# AMS_TNN_V1_0.net
KiCad netlist of a schematic drawn in EAGLE
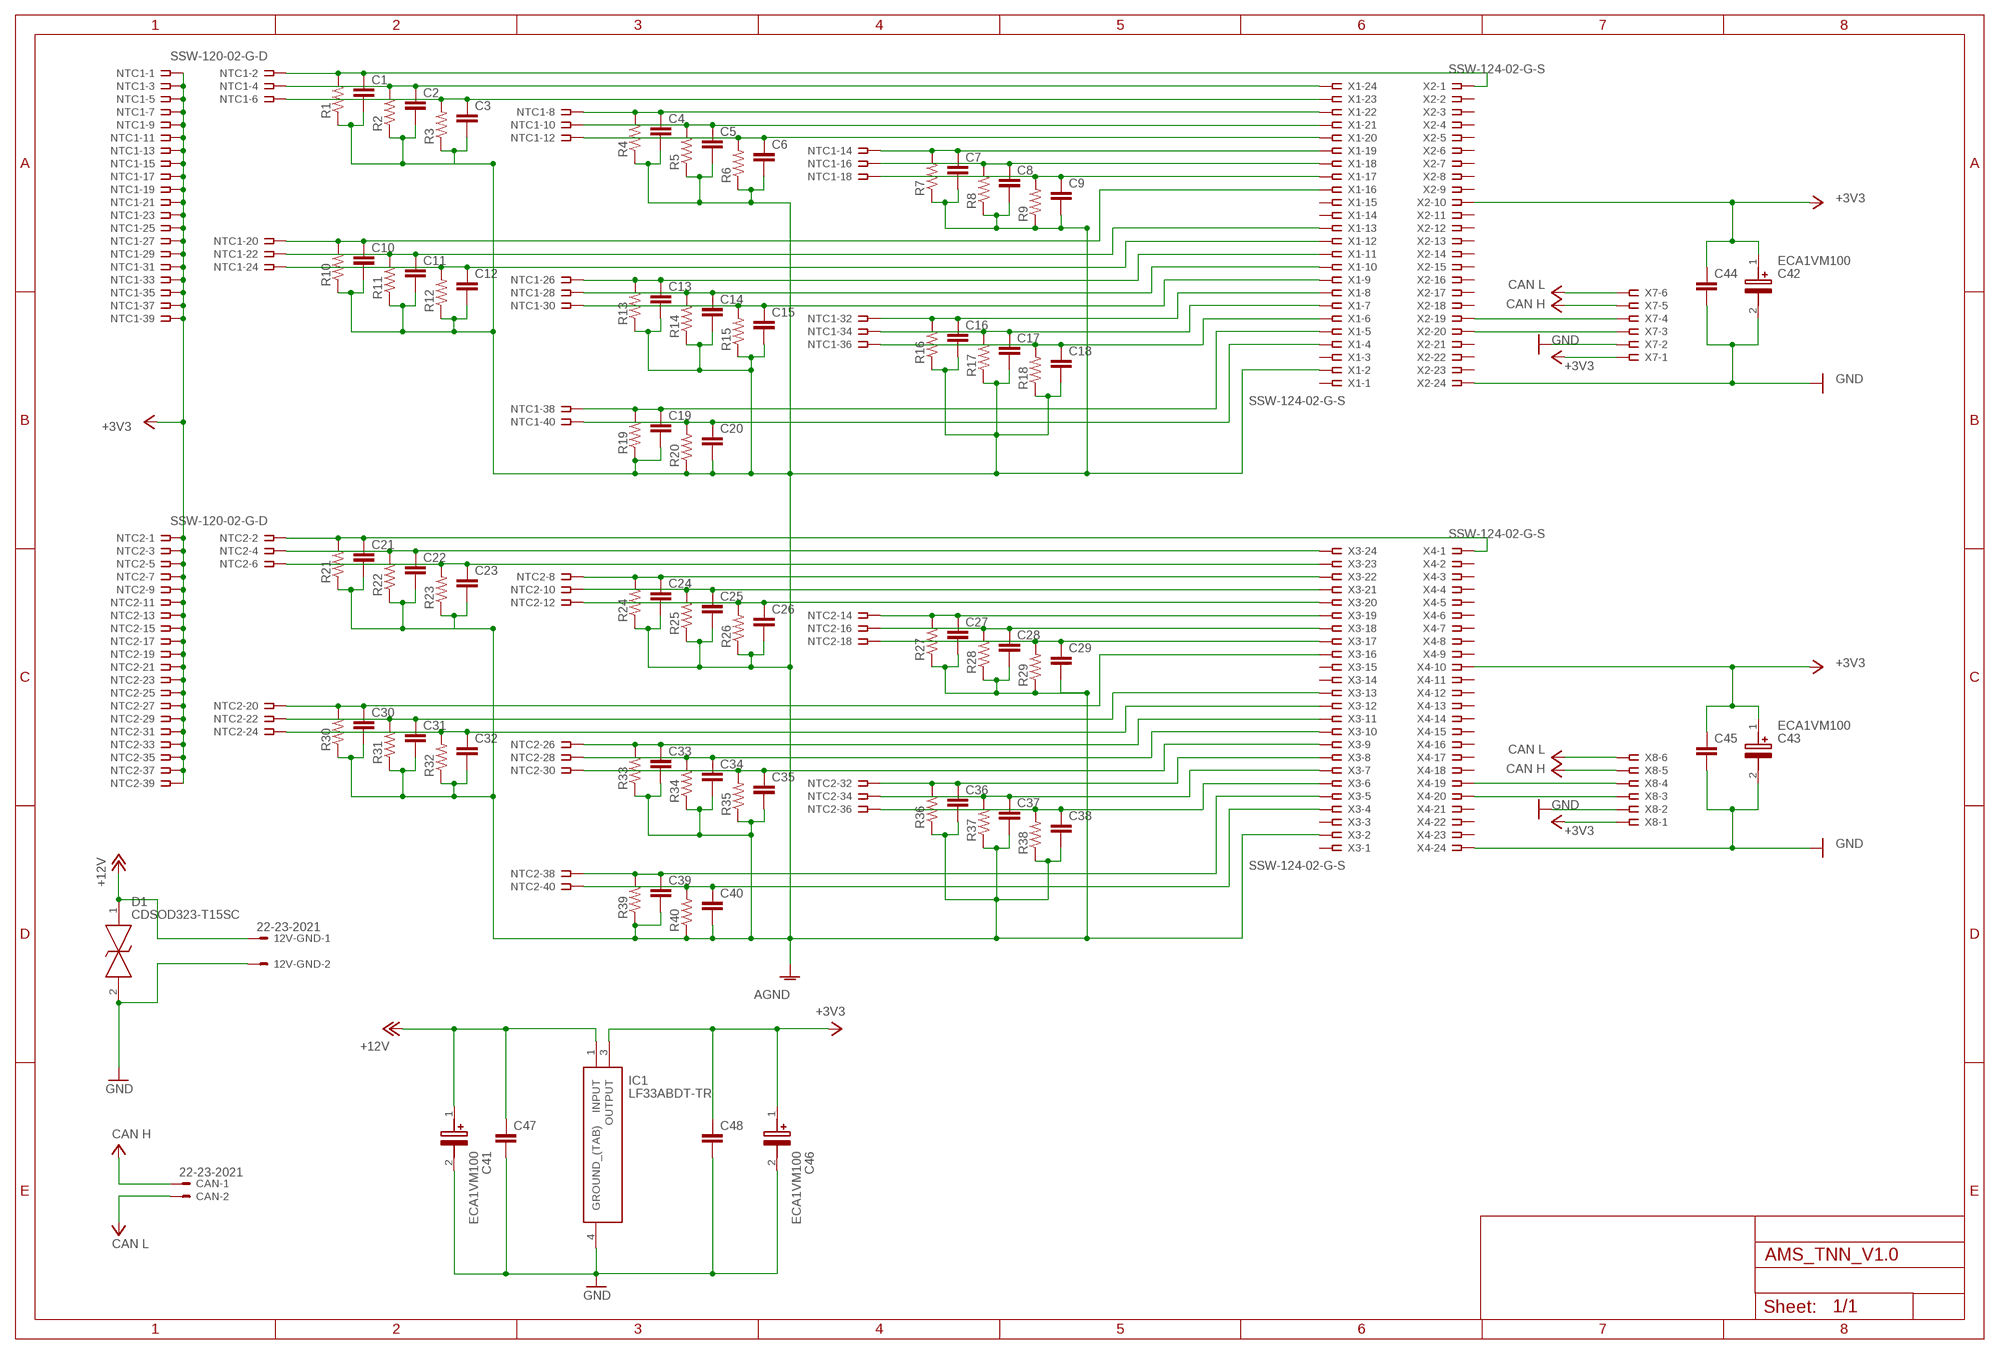
[diagram p0: schematic, sheet 1]

(export (version "E")
  (design (tool "Eeschema 10.0.6"))
  (components
    (comp (ref "12V-GND")
      (value "22-23-2021")
      (footprint "eagle-import:22-23-2021")
      (fields (field (name "MF") "MOLEX"))
      (libsource (lib "eagle-import") (part "22-23-2021"))
    )
    (comp (ref "C1")
      (value "C-EUC0603")
      (footprint "eagle-import:C0603")
      (libsource (lib "eagle-import") (part "C-EUC0603"))
    )
    (comp (ref "C2")
      (value "C-EUC0603")
      (footprint "eagle-import:C0603")
      (libsource (lib "eagle-import") (part "C-EUC0603"))
    )
    (comp (ref "C3")
      (value "C-EUC0603")
      (footprint "eagle-import:C0603")
      (libsource (lib "eagle-import") (part "C-EUC0603"))
    )
    (comp (ref "C4")
      (value "C-EUC0603")
      (footprint "eagle-import:C0603")
      (libsource (lib "eagle-import") (part "C-EUC0603"))
    )
    (comp (ref "C5")
      (value "C-EUC0603")
      (footprint "eagle-import:C0603")
      (libsource (lib "eagle-import") (part "C-EUC0603"))
    )
    (comp (ref "C6")
      (value "C-EUC0603")
      (footprint "eagle-import:C0603")
      (libsource (lib "eagle-import") (part "C-EUC0603"))
    )
    (comp (ref "C7")
      (value "C-EUC0603")
      (footprint "eagle-import:C0603")
      (libsource (lib "eagle-import") (part "C-EUC0603"))
    )
    (comp (ref "C8")
      (value "C-EUC0603")
      (footprint "eagle-import:C0603")
      (libsource (lib "eagle-import") (part "C-EUC0603"))
    )
    (comp (ref "C9")
      (value "C-EUC0603")
      (footprint "eagle-import:C0603")
      (libsource (lib "eagle-import") (part "C-EUC0603"))
    )
    (comp (ref "C10")
      (value "C-EUC0603")
      (footprint "eagle-import:C0603")
      (libsource (lib "eagle-import") (part "C-EUC0603"))
    )
    (comp (ref "C11")
      (value "C-EUC0603")
      (footprint "eagle-import:C0603")
      (libsource (lib "eagle-import") (part "C-EUC0603"))
    )
    (comp (ref "C12")
      (value "C-EUC0603")
      (footprint "eagle-import:C0603")
      (libsource (lib "eagle-import") (part "C-EUC0603"))
    )
    (comp (ref "C13")
      (value "C-EUC0603")
      (footprint "eagle-import:C0603")
      (libsource (lib "eagle-import") (part "C-EUC0603"))
    )
    (comp (ref "C14")
      (value "C-EUC0603")
      (footprint "eagle-import:C0603")
      (libsource (lib "eagle-import") (part "C-EUC0603"))
    )
    (comp (ref "C15")
      (value "C-EUC0603")
      (footprint "eagle-import:C0603")
      (libsource (lib "eagle-import") (part "C-EUC0603"))
    )
    (comp (ref "C16")
      (value "C-EUC0603")
      (footprint "eagle-import:C0603")
      (libsource (lib "eagle-import") (part "C-EUC0603"))
    )
    (comp (ref "C17")
      (value "C-EUC0603")
      (footprint "eagle-import:C0603")
      (libsource (lib "eagle-import") (part "C-EUC0603"))
    )
    (comp (ref "C18")
      (value "C-EUC0603")
      (footprint "eagle-import:C0603")
      (libsource (lib "eagle-import") (part "C-EUC0603"))
    )
    (comp (ref "C19")
      (value "C-EUC0603")
      (footprint "eagle-import:C0603")
      (libsource (lib "eagle-import") (part "C-EUC0603"))
    )
    (comp (ref "C20")
      (value "C-EUC0603")
      (footprint "eagle-import:C0603")
      (libsource (lib "eagle-import") (part "C-EUC0603"))
    )
    (comp (ref "C21")
      (value "C-EUC0603")
      (footprint "eagle-import:C0603")
      (libsource (lib "eagle-import") (part "C-EUC0603"))
    )
    (comp (ref "C22")
      (value "C-EUC0603")
      (footprint "eagle-import:C0603")
      (libsource (lib "eagle-import") (part "C-EUC0603"))
    )
    (comp (ref "C23")
      (value "C-EUC0603")
      (footprint "eagle-import:C0603")
      (libsource (lib "eagle-import") (part "C-EUC0603"))
    )
    (comp (ref "C24")
      (value "C-EUC0603")
      (footprint "eagle-import:C0603")
      (libsource (lib "eagle-import") (part "C-EUC0603"))
    )
    (comp (ref "C25")
      (value "C-EUC0603")
      (footprint "eagle-import:C0603")
      (libsource (lib "eagle-import") (part "C-EUC0603"))
    )
    (comp (ref "C26")
      (value "C-EUC0603")
      (footprint "eagle-import:C0603")
      (libsource (lib "eagle-import") (part "C-EUC0603"))
    )
    (comp (ref "C27")
      (value "C-EUC0603")
      (footprint "eagle-import:C0603")
      (libsource (lib "eagle-import") (part "C-EUC0603"))
    )
    (comp (ref "C28")
      (value "C-EUC0603")
      (footprint "eagle-import:C0603")
      (libsource (lib "eagle-import") (part "C-EUC0603"))
    )
    (comp (ref "C29")
      (value "C-EUC0603")
      (footprint "eagle-import:C0603")
      (libsource (lib "eagle-import") (part "C-EUC0603"))
    )
    (comp (ref "C30")
      (value "C-EUC0603")
      (footprint "eagle-import:C0603")
      (libsource (lib "eagle-import") (part "C-EUC0603"))
    )
    (comp (ref "C31")
      (value "C-EUC0603")
      (footprint "eagle-import:C0603")
      (libsource (lib "eagle-import") (part "C-EUC0603"))
    )
    (comp (ref "C32")
      (value "C-EUC0603")
      (footprint "eagle-import:C0603")
      (libsource (lib "eagle-import") (part "C-EUC0603"))
    )
    (comp (ref "C33")
      (value "C-EUC0603")
      (footprint "eagle-import:C0603")
      (libsource (lib "eagle-import") (part "C-EUC0603"))
    )
    (comp (ref "C34")
      (value "C-EUC0603")
      (footprint "eagle-import:C0603")
      (libsource (lib "eagle-import") (part "C-EUC0603"))
    )
    (comp (ref "C35")
      (value "C-EUC0603")
      (footprint "eagle-import:C0603")
      (libsource (lib "eagle-import") (part "C-EUC0603"))
    )
    (comp (ref "C36")
      (value "C-EUC0603")
      (footprint "eagle-import:C0603")
      (libsource (lib "eagle-import") (part "C-EUC0603"))
    )
    (comp (ref "C37")
      (value "C-EUC0603")
      (footprint "eagle-import:C0603")
      (libsource (lib "eagle-import") (part "C-EUC0603"))
    )
    (comp (ref "C38")
      (value "C-EUC0603")
      (footprint "eagle-import:C0603")
      (libsource (lib "eagle-import") (part "C-EUC0603"))
    )
    (comp (ref "C39")
      (value "C-EUC0603")
      (footprint "eagle-import:C0603")
      (libsource (lib "eagle-import") (part "C-EUC0603"))
    )
    (comp (ref "C40")
      (value "C-EUC0603")
      (footprint "eagle-import:C0603")
      (libsource (lib "eagle-import") (part "C-EUC0603"))
    )
    (comp (ref "C41")
      (value "ECA1VM100")
      (footprint "eagle-import:CAPPRD200W55D525H1200")
      (libsource (lib "eagle-import") (part "ECA1VM100"))
    )
    (comp (ref "C42")
      (value "ECA1VM100")
      (footprint "eagle-import:CAPPRD200W55D525H1200")
      (libsource (lib "eagle-import") (part "ECA1VM100"))
    )
    (comp (ref "C43")
      (value "ECA1VM100")
      (footprint "eagle-import:CAPPRD200W55D525H1200")
      (libsource (lib "eagle-import") (part "ECA1VM100"))
    )
    (comp (ref "C44")
      (value "C-EUC0603")
      (footprint "eagle-import:C0603")
      (libsource (lib "eagle-import") (part "C-EUC0603"))
    )
    (comp (ref "C45")
      (value "C-EUC0603")
      (footprint "eagle-import:C0603")
      (libsource (lib "eagle-import") (part "C-EUC0603"))
    )
    (comp (ref "C46")
      (value "ECA1VM100")
      (footprint "eagle-import:CAPPRD200W55D525H1200")
      (libsource (lib "eagle-import") (part "ECA1VM100"))
    )
    (comp (ref "C47")
      (value "C-EUC0603")
      (footprint "eagle-import:C0603")
      (libsource (lib "eagle-import") (part "C-EUC0603"))
    )
    (comp (ref "C48")
      (value "C-EUC0603")
      (footprint "eagle-import:C0603")
      (libsource (lib "eagle-import") (part "C-EUC0603"))
    )
    (comp (ref "CAN")
      (value "22-23-2021")
      (footprint "eagle-import:22-23-2021")
      (fields (field (name "MF") "MOLEX"))
      (libsource (lib "eagle-import") (part "22-23-2021"))
    )
    (comp (ref "D1")
      (value "CDSOD323-T15SC")
      (footprint "eagle-import:SOD-323")
      (fields (field (name "MOUSER_PART_NUMBER") "652-CDSOD323-T15SC"))
      (libsource (lib "eagle-import") (part "CDSOD323-T15SC"))
    )
    (comp (ref "IC1")
      (value "LF33ABDT-TR")
      (footprint "eagle-import:TO228P972X240-3N")
      (fields (field (name "MOUSER_PART_NUMBER") "511-LF33ABDT-TR"))
      (libsource (lib "eagle-import") (part "LF33ABDT-TR"))
    )
    (comp (ref "NTC1")
      (value "SSW-120-02-G-D")
      (footprint "eagle-import:SSW-120-02-G-D")
      (fields (field (name "MF") "Samtec Inc."))
      (libsource (lib "eagle-import") (part "SSW-120-02-G-D"))
    )
    (comp (ref "NTC2")
      (value "SSW-120-02-G-D")
      (footprint "eagle-import:SSW-120-02-G-D")
      (fields (field (name "MF") "Samtec Inc."))
      (libsource (lib "eagle-import") (part "SSW-120-02-G-D"))
    )
    (comp (ref "R1")
      (value "R-US_R0603")
      (footprint "eagle-import:R0603")
      (libsource (lib "eagle-import") (part "R-US_R0603"))
    )
    (comp (ref "R2")
      (value "R-US_R0603")
      (footprint "eagle-import:R0603")
      (libsource (lib "eagle-import") (part "R-US_R0603"))
    )
    (comp (ref "R3")
      (value "R-US_R0603")
      (footprint "eagle-import:R0603")
      (libsource (lib "eagle-import") (part "R-US_R0603"))
    )
    (comp (ref "R4")
      (value "R-US_R0603")
      (footprint "eagle-import:R0603")
      (libsource (lib "eagle-import") (part "R-US_R0603"))
    )
    (comp (ref "R5")
      (value "R-US_R0603")
      (footprint "eagle-import:R0603")
      (libsource (lib "eagle-import") (part "R-US_R0603"))
    )
    (comp (ref "R6")
      (value "R-US_R0603")
      (footprint "eagle-import:R0603")
      (libsource (lib "eagle-import") (part "R-US_R0603"))
    )
    (comp (ref "R7")
      (value "R-US_R0603")
      (footprint "eagle-import:R0603")
      (libsource (lib "eagle-import") (part "R-US_R0603"))
    )
    (comp (ref "R8")
      (value "R-US_R0603")
      (footprint "eagle-import:R0603")
      (libsource (lib "eagle-import") (part "R-US_R0603"))
    )
    (comp (ref "R9")
      (value "R-US_R0603")
      (footprint "eagle-import:R0603")
      (libsource (lib "eagle-import") (part "R-US_R0603"))
    )
    (comp (ref "R10")
      (value "R-US_R0603")
      (footprint "eagle-import:R0603")
      (libsource (lib "eagle-import") (part "R-US_R0603"))
    )
    (comp (ref "R11")
      (value "R-US_R0603")
      (footprint "eagle-import:R0603")
      (libsource (lib "eagle-import") (part "R-US_R0603"))
    )
    (comp (ref "R12")
      (value "R-US_R0603")
      (footprint "eagle-import:R0603")
      (libsource (lib "eagle-import") (part "R-US_R0603"))
    )
    (comp (ref "R13")
      (value "R-US_R0603")
      (footprint "eagle-import:R0603")
      (libsource (lib "eagle-import") (part "R-US_R0603"))
    )
    (comp (ref "R14")
      (value "R-US_R0603")
      (footprint "eagle-import:R0603")
      (libsource (lib "eagle-import") (part "R-US_R0603"))
    )
    (comp (ref "R15")
      (value "R-US_R0603")
      (footprint "eagle-import:R0603")
      (libsource (lib "eagle-import") (part "R-US_R0603"))
    )
    (comp (ref "R16")
      (value "R-US_R0603")
      (footprint "eagle-import:R0603")
      (libsource (lib "eagle-import") (part "R-US_R0603"))
    )
    (comp (ref "R17")
      (value "R-US_R0603")
      (footprint "eagle-import:R0603")
      (libsource (lib "eagle-import") (part "R-US_R0603"))
    )
    (comp (ref "R18")
      (value "R-US_R0603")
      (footprint "eagle-import:R0603")
      (libsource (lib "eagle-import") (part "R-US_R0603"))
    )
    (comp (ref "R19")
      (value "R-US_R0603")
      (footprint "eagle-import:R0603")
      (libsource (lib "eagle-import") (part "R-US_R0603"))
    )
    (comp (ref "R20")
      (value "R-US_R0603")
      (footprint "eagle-import:R0603")
      (libsource (lib "eagle-import") (part "R-US_R0603"))
    )
    (comp (ref "R21")
      (value "R-US_R0603")
      (footprint "eagle-import:R0603")
      (libsource (lib "eagle-import") (part "R-US_R0603"))
    )
    (comp (ref "R22")
      (value "R-US_R0603")
      (footprint "eagle-import:R0603")
      (libsource (lib "eagle-import") (part "R-US_R0603"))
    )
    (comp (ref "R23")
      (value "R-US_R0603")
      (footprint "eagle-import:R0603")
      (libsource (lib "eagle-import") (part "R-US_R0603"))
    )
    (comp (ref "R24")
      (value "R-US_R0603")
      (footprint "eagle-import:R0603")
      (libsource (lib "eagle-import") (part "R-US_R0603"))
    )
    (comp (ref "R25")
      (value "R-US_R0603")
      (footprint "eagle-import:R0603")
      (libsource (lib "eagle-import") (part "R-US_R0603"))
    )
    (comp (ref "R26")
      (value "R-US_R0603")
      (footprint "eagle-import:R0603")
      (libsource (lib "eagle-import") (part "R-US_R0603"))
    )
    (comp (ref "R27")
      (value "R-US_R0603")
      (footprint "eagle-import:R0603")
      (libsource (lib "eagle-import") (part "R-US_R0603"))
    )
    (comp (ref "R28")
      (value "R-US_R0603")
      (footprint "eagle-import:R0603")
      (libsource (lib "eagle-import") (part "R-US_R0603"))
    )
    (comp (ref "R29")
      (value "R-US_R0603")
      (footprint "eagle-import:R0603")
      (libsource (lib "eagle-import") (part "R-US_R0603"))
    )
    (comp (ref "R30")
      (value "R-US_R0603")
      (footprint "eagle-import:R0603")
      (libsource (lib "eagle-import") (part "R-US_R0603"))
    )
    (comp (ref "R31")
      (value "R-US_R0603")
      (footprint "eagle-import:R0603")
      (libsource (lib "eagle-import") (part "R-US_R0603"))
    )
    (comp (ref "R32")
      (value "R-US_R0603")
      (footprint "eagle-import:R0603")
      (libsource (lib "eagle-import") (part "R-US_R0603"))
    )
    (comp (ref "R33")
      (value "R-US_R0603")
      (footprint "eagle-import:R0603")
      (libsource (lib "eagle-import") (part "R-US_R0603"))
    )
    (comp (ref "R34")
      (value "R-US_R0603")
      (footprint "eagle-import:R0603")
      (libsource (lib "eagle-import") (part "R-US_R0603"))
    )
    (comp (ref "R35")
      (value "R-US_R0603")
      (footprint "eagle-import:R0603")
      (libsource (lib "eagle-import") (part "R-US_R0603"))
    )
    (comp (ref "R36")
      (value "R-US_R0603")
      (footprint "eagle-import:R0603")
      (libsource (lib "eagle-import") (part "R-US_R0603"))
    )
    (comp (ref "R37")
      (value "R-US_R0603")
      (footprint "eagle-import:R0603")
      (libsource (lib "eagle-import") (part "R-US_R0603"))
    )
    (comp (ref "R38")
      (value "R-US_R0603")
      (footprint "eagle-import:R0603")
      (libsource (lib "eagle-import") (part "R-US_R0603"))
    )
    (comp (ref "R39")
      (value "R-US_R0603")
      (footprint "eagle-import:R0603")
      (libsource (lib "eagle-import") (part "R-US_R0603"))
    )
    (comp (ref "R40")
      (value "R-US_R0603")
      (footprint "eagle-import:R0603")
      (libsource (lib "eagle-import") (part "R-US_R0603"))
    )
    (comp (ref "X1")
      (value "SSW-124-02-G-S")
      (footprint "eagle-import:SSW-124-02-G-S")
      (fields (field (name "MF") "Samtec Inc."))
      (libsource (lib "eagle-import") (part "SSW-124-02-G-S"))
    )
    (comp (ref "X2")
      (value "SSW-124-02-G-S")
      (footprint "eagle-import:SSW-124-02-G-S")
      (fields (field (name "MF") "Samtec Inc."))
      (libsource (lib "eagle-import") (part "SSW-124-02-G-S"))
    )
    (comp (ref "X3")
      (value "SSW-124-02-G-S")
      (footprint "eagle-import:SSW-124-02-G-S")
      (fields (field (name "MF") "Samtec Inc."))
      (libsource (lib "eagle-import") (part "SSW-124-02-G-S"))
    )
    (comp (ref "X4")
      (value "SSW-124-02-G-S")
      (footprint "eagle-import:SSW-124-02-G-S")
      (fields (field (name "MF") "Samtec Inc."))
      (libsource (lib "eagle-import") (part "SSW-124-02-G-S"))
    )
    (comp (ref "X7")
      (value "SSW-106-02-G-S")
      (footprint "eagle-import:SSW-106-02-G-S")
      (fields (field (name "MF") "Samtec Inc."))
      (libsource (lib "eagle-import") (part "SSW-106-02-G-S"))
    )
    (comp (ref "X8")
      (value "SSW-106-02-G-S")
      (footprint "eagle-import:SSW-106-02-G-S")
      (fields (field (name "MF") "Samtec Inc."))
      (libsource (lib "eagle-import") (part "SSW-106-02-G-S"))
    )
  )
  (nets
    (net (code "1") (name "+3V3") (class "Default")
      (node (ref "C42") (pin "1") (pinfunction "+_1") (pintype "bidirectional"))
      (node (ref "C43") (pin "1") (pinfunction "+_1") (pintype "bidirectional"))
      (node (ref "C44") (pin "1") (pinfunction "1_1") (pintype "passive"))
      (node (ref "C45") (pin "1") (pinfunction "1_1") (pintype "passive"))
      (node (ref "C46") (pin "1") (pinfunction "+_1") (pintype "bidirectional"))
      (node (ref "C48") (pin "1") (pinfunction "1_1") (pintype "passive"))
      (node (ref "IC1") (pin "3") (pinfunction "OUTPUT_3") (pintype "output"))
      (node (ref "NTC1") (pin "1") (pinfunction "1_1") (pintype "passive"))
      (node (ref "NTC1") (pin "11") (pinfunction "1_11") (pintype "passive"))
      (node (ref "NTC1") (pin "13") (pinfunction "1_13") (pintype "passive"))
      (node (ref "NTC1") (pin "15") (pinfunction "1_15") (pintype "passive"))
      (node (ref "NTC1") (pin "17") (pinfunction "1_17") (pintype "passive"))
      (node (ref "NTC1") (pin "19") (pinfunction "1_19") (pintype "passive"))
      (node (ref "NTC1") (pin "21") (pinfunction "1_21") (pintype "passive"))
      (node (ref "NTC1") (pin "23") (pinfunction "1_23") (pintype "passive"))
      (node (ref "NTC1") (pin "25") (pinfunction "1_25") (pintype "passive"))
      (node (ref "NTC1") (pin "27") (pinfunction "1_27") (pintype "passive"))
      (node (ref "NTC1") (pin "29") (pinfunction "1_29") (pintype "passive"))
      (node (ref "NTC1") (pin "3") (pinfunction "1_3") (pintype "passive"))
      (node (ref "NTC1") (pin "31") (pinfunction "1_31") (pintype "passive"))
      (node (ref "NTC1") (pin "33") (pinfunction "1_33") (pintype "passive"))
      (node (ref "NTC1") (pin "35") (pinfunction "1_35") (pintype "passive"))
      (node (ref "NTC1") (pin "37") (pinfunction "1_37") (pintype "passive"))
      (node (ref "NTC1") (pin "39") (pinfunction "1_39") (pintype "passive"))
      (node (ref "NTC1") (pin "5") (pinfunction "1_5") (pintype "passive"))
      (node (ref "NTC1") (pin "7") (pinfunction "1_7") (pintype "passive"))
      (node (ref "NTC1") (pin "9") (pinfunction "1_9") (pintype "passive"))
      (node (ref "NTC2") (pin "1") (pinfunction "1_1") (pintype "passive"))
      (node (ref "NTC2") (pin "11") (pinfunction "1_11") (pintype "passive"))
      (node (ref "NTC2") (pin "13") (pinfunction "1_13") (pintype "passive"))
      (node (ref "NTC2") (pin "15") (pinfunction "1_15") (pintype "passive"))
      (node (ref "NTC2") (pin "17") (pinfunction "1_17") (pintype "passive"))
      (node (ref "NTC2") (pin "19") (pinfunction "1_19") (pintype "passive"))
      (node (ref "NTC2") (pin "21") (pinfunction "1_21") (pintype "passive"))
      (node (ref "NTC2") (pin "23") (pinfunction "1_23") (pintype "passive"))
      (node (ref "NTC2") (pin "25") (pinfunction "1_25") (pintype "passive"))
      (node (ref "NTC2") (pin "27") (pinfunction "1_27") (pintype "passive"))
      (node (ref "NTC2") (pin "29") (pinfunction "1_29") (pintype "passive"))
      (node (ref "NTC2") (pin "3") (pinfunction "1_3") (pintype "passive"))
      (node (ref "NTC2") (pin "31") (pinfunction "1_31") (pintype "passive"))
      (node (ref "NTC2") (pin "33") (pinfunction "1_33") (pintype "passive"))
      (node (ref "NTC2") (pin "35") (pinfunction "1_35") (pintype "passive"))
      (node (ref "NTC2") (pin "37") (pinfunction "1_37") (pintype "passive"))
      (node (ref "NTC2") (pin "39") (pinfunction "1_39") (pintype "passive"))
      (node (ref "NTC2") (pin "5") (pinfunction "1_5") (pintype "passive"))
      (node (ref "NTC2") (pin "7") (pinfunction "1_7") (pintype "passive"))
      (node (ref "NTC2") (pin "9") (pinfunction "1_9") (pintype "passive"))
      (node (ref "X2") (pin "10") (pinfunction "1_10") (pintype "passive"))
      (node (ref "X4") (pin "10") (pinfunction "1_10") (pintype "passive"))
      (node (ref "X7") (pin "1") (pinfunction "1_1") (pintype "passive"))
      (node (ref "X8") (pin "1") (pinfunction "1_1") (pintype "passive"))
    )
    (net (code "2") (name "+12V") (class "Default")
      (node (ref "12V-GND") (pin "1") (pinfunction "S_1") (pintype "passive"))
      (node (ref "C41") (pin "1") (pinfunction "+_1") (pintype "bidirectional"))
      (node (ref "C47") (pin "1") (pinfunction "1_1") (pintype "passive"))
      (node (ref "D1") (pin "1") (pinfunction "1_1") (pintype "bidirectional"))
      (node (ref "IC1") (pin "1") (pinfunction "INPUT_1") (pintype "input"))
    )
    (net (code "3") (name "AGND") (class "Default")
      (node (ref "C1") (pin "2") (pinfunction "2_2") (pintype "passive"))
      (node (ref "C10") (pin "2") (pinfunction "2_2") (pintype "passive"))
      (node (ref "C11") (pin "2") (pinfunction "2_2") (pintype "passive"))
      (node (ref "C12") (pin "2") (pinfunction "2_2") (pintype "passive"))
      (node (ref "C13") (pin "2") (pinfunction "2_2") (pintype "passive"))
      (node (ref "C14") (pin "2") (pinfunction "2_2") (pintype "passive"))
      (node (ref "C15") (pin "2") (pinfunction "2_2") (pintype "passive"))
      (node (ref "C16") (pin "2") (pinfunction "2_2") (pintype "passive"))
      (node (ref "C17") (pin "2") (pinfunction "2_2") (pintype "passive"))
      (node (ref "C18") (pin "2") (pinfunction "2_2") (pintype "passive"))
      (node (ref "C19") (pin "2") (pinfunction "2_2") (pintype "passive"))
      (node (ref "C2") (pin "2") (pinfunction "2_2") (pintype "passive"))
      (node (ref "C20") (pin "2") (pinfunction "2_2") (pintype "passive"))
      (node (ref "C21") (pin "2") (pinfunction "2_2") (pintype "passive"))
      (node (ref "C22") (pin "2") (pinfunction "2_2") (pintype "passive"))
      (node (ref "C23") (pin "2") (pinfunction "2_2") (pintype "passive"))
      (node (ref "C24") (pin "2") (pinfunction "2_2") (pintype "passive"))
      (node (ref "C25") (pin "2") (pinfunction "2_2") (pintype "passive"))
      (node (ref "C26") (pin "2") (pinfunction "2_2") (pintype "passive"))
      (node (ref "C27") (pin "2") (pinfunction "2_2") (pintype "passive"))
      (node (ref "C28") (pin "2") (pinfunction "2_2") (pintype "passive"))
      (node (ref "C29") (pin "2") (pinfunction "2_2") (pintype "passive"))
      (node (ref "C3") (pin "2") (pinfunction "2_2") (pintype "passive"))
      (node (ref "C30") (pin "2") (pinfunction "2_2") (pintype "passive"))
      (node (ref "C31") (pin "2") (pinfunction "2_2") (pintype "passive"))
      (node (ref "C32") (pin "2") (pinfunction "2_2") (pintype "passive"))
      (node (ref "C33") (pin "2") (pinfunction "2_2") (pintype "passive"))
      (node (ref "C34") (pin "2") (pinfunction "2_2") (pintype "passive"))
      (node (ref "C35") (pin "2") (pinfunction "2_2") (pintype "passive"))
      (node (ref "C36") (pin "2") (pinfunction "2_2") (pintype "passive"))
      (node (ref "C37") (pin "2") (pinfunction "2_2") (pintype "passive"))
      (node (ref "C38") (pin "2") (pinfunction "2_2") (pintype "passive"))
      (node (ref "C39") (pin "2") (pinfunction "2_2") (pintype "passive"))
      (node (ref "C4") (pin "2") (pinfunction "2_2") (pintype "passive"))
      (node (ref "C40") (pin "2") (pinfunction "2_2") (pintype "passive"))
      (node (ref "C5") (pin "2") (pinfunction "2_2") (pintype "passive"))
      (node (ref "C6") (pin "2") (pinfunction "2_2") (pintype "passive"))
      (node (ref "C7") (pin "2") (pinfunction "2_2") (pintype "passive"))
      (node (ref "C8") (pin "2") (pinfunction "2_2") (pintype "passive"))
      (node (ref "C9") (pin "2") (pinfunction "2_2") (pintype "passive"))
      (node (ref "R1") (pin "1") (pinfunction "1_1") (pintype "passive"))
      (node (ref "R10") (pin "1") (pinfunction "1_1") (pintype "passive"))
      (node (ref "R11") (pin "1") (pinfunction "1_1") (pintype "passive"))
      (node (ref "R12") (pin "1") (pinfunction "1_1") (pintype "passive"))
      (node (ref "R13") (pin "1") (pinfunction "1_1") (pintype "passive"))
      (node (ref "R14") (pin "1") (pinfunction "1_1") (pintype "passive"))
      (node (ref "R15") (pin "1") (pinfunction "1_1") (pintype "passive"))
      (node (ref "R16") (pin "1") (pinfunction "1_1") (pintype "passive"))
      (node (ref "R17") (pin "1") (pinfunction "1_1") (pintype "passive"))
      (node (ref "R18") (pin "1") (pinfunction "1_1") (pintype "passive"))
      (node (ref "R19") (pin "1") (pinfunction "1_1") (pintype "passive"))
      (node (ref "R2") (pin "1") (pinfunction "1_1") (pintype "passive"))
      (node (ref "R20") (pin "1") (pinfunction "1_1") (pintype "passive"))
      (node (ref "R21") (pin "1") (pinfunction "1_1") (pintype "passive"))
      (node (ref "R22") (pin "1") (pinfunction "1_1") (pintype "passive"))
      (node (ref "R23") (pin "1") (pinfunction "1_1") (pintype "passive"))
      (node (ref "R24") (pin "1") (pinfunction "1_1") (pintype "passive"))
      (node (ref "R25") (pin "1") (pinfunction "1_1") (pintype "passive"))
      (node (ref "R26") (pin "1") (pinfunction "1_1") (pintype "passive"))
      (node (ref "R27") (pin "1") (pinfunction "1_1") (pintype "passive"))
      (node (ref "R28") (pin "1") (pinfunction "1_1") (pintype "passive"))
      (node (ref "R29") (pin "1") (pinfunction "1_1") (pintype "passive"))
      (node (ref "R3") (pin "1") (pinfunction "1_1") (pintype "passive"))
      (node (ref "R30") (pin "1") (pinfunction "1_1") (pintype "passive"))
      (node (ref "R31") (pin "1") (pinfunction "1_1") (pintype "passive"))
      (node (ref "R32") (pin "1") (pinfunction "1_1") (pintype "passive"))
      (node (ref "R33") (pin "1") (pinfunction "1_1") (pintype "passive"))
      (node (ref "R34") (pin "1") (pinfunction "1_1") (pintype "passive"))
      (node (ref "R35") (pin "1") (pinfunction "1_1") (pintype "passive"))
      (node (ref "R36") (pin "1") (pinfunction "1_1") (pintype "passive"))
      (node (ref "R37") (pin "1") (pinfunction "1_1") (pintype "passive"))
      (node (ref "R38") (pin "1") (pinfunction "1_1") (pintype "passive"))
      (node (ref "R39") (pin "1") (pinfunction "1_1") (pintype "passive"))
      (node (ref "R4") (pin "1") (pinfunction "1_1") (pintype "passive"))
      (node (ref "R40") (pin "1") (pinfunction "1_1") (pintype "passive"))
      (node (ref "R5") (pin "1") (pinfunction "1_1") (pintype "passive"))
      (node (ref "R6") (pin "1") (pinfunction "1_1") (pintype "passive"))
      (node (ref "R7") (pin "1") (pinfunction "1_1") (pintype "passive"))
      (node (ref "R8") (pin "1") (pinfunction "1_1") (pintype "passive"))
      (node (ref "R9") (pin "1") (pinfunction "1_1") (pintype "passive"))
      (node (ref "X1") (pin "2") (pinfunction "1_2") (pintype "passive"))
      (node (ref "X3") (pin "2") (pinfunction "1_2") (pintype "passive"))
    )
    (net (code "4") (name "CAN H") (class "Default")
      (node (ref "CAN") (pin "1") (pinfunction "S_1") (pintype "passive"))
      (node (ref "X7") (pin "5") (pinfunction "1_5") (pintype "passive"))
      (node (ref "X8") (pin "5") (pinfunction "1_5") (pintype "passive"))
    )
    (net (code "5") (name "CAN L") (class "Default")
      (node (ref "CAN") (pin "2") (pinfunction "S_2") (pintype "passive"))
      (node (ref "X7") (pin "6") (pinfunction "1_6") (pintype "passive"))
      (node (ref "X8") (pin "6") (pinfunction "1_6") (pintype "passive"))
    )
    (net (code "6") (name "GND") (class "Default")
      (node (ref "12V-GND") (pin "2") (pinfunction "S_2") (pintype "passive"))
      (node (ref "C41") (pin "2") (pinfunction "-_2") (pintype "bidirectional"))
      (node (ref "C42") (pin "2") (pinfunction "-_2") (pintype "bidirectional"))
      (node (ref "C43") (pin "2") (pinfunction "-_2") (pintype "bidirectional"))
      (node (ref "C44") (pin "2") (pinfunction "2_2") (pintype "passive"))
      (node (ref "C45") (pin "2") (pinfunction "2_2") (pintype "passive"))
      (node (ref "C46") (pin "2") (pinfunction "-_2") (pintype "bidirectional"))
      (node (ref "C47") (pin "2") (pinfunction "2_2") (pintype "passive"))
      (node (ref "C48") (pin "2") (pinfunction "2_2") (pintype "passive"))
      (node (ref "D1") (pin "2") (pinfunction "2_2") (pintype "bidirectional"))
      (node (ref "IC1") (pin "4") (pinfunction "GROUND_(TAB)_4") (pintype "bidirectional"))
      (node (ref "X2") (pin "24") (pinfunction "1_24") (pintype "passive"))
      (node (ref "X4") (pin "24") (pinfunction "1_24") (pintype "passive"))
      (node (ref "X7") (pin "2") (pinfunction "1_2") (pintype "passive"))
      (node (ref "X8") (pin "2") (pinfunction "1_2") (pintype "passive"))
    )
    (net (code "7") (name "Net-(NTC1AB-1)") (class "Default")
      (node (ref "C17") (pin "1") (pinfunction "1_1") (pintype "passive"))
      (node (ref "NTC1") (pin "34") (pinfunction "1_34") (pintype "passive"))
      (node (ref "R17") (pin "2") (pinfunction "2_2") (pintype "passive"))
      (node (ref "X1") (pin "7") (pinfunction "1_7") (pintype "passive"))
    )
    (net (code "8") (name "Net-(NTC1AD-1)") (class "Default")
      (node (ref "C18") (pin "1") (pinfunction "1_1") (pintype "passive"))
      (node (ref "NTC1") (pin "36") (pinfunction "1_36") (pintype "passive"))
      (node (ref "R18") (pin "2") (pinfunction "2_2") (pintype "passive"))
      (node (ref "X1") (pin "6") (pinfunction "1_6") (pintype "passive"))
    )
    (net (code "9") (name "Net-(NTC1AF-1)") (class "Default")
      (node (ref "C19") (pin "1") (pinfunction "1_1") (pintype "passive"))
      (node (ref "NTC1") (pin "38") (pinfunction "1_38") (pintype "passive"))
      (node (ref "R19") (pin "2") (pinfunction "2_2") (pintype "passive"))
      (node (ref "X1") (pin "5") (pinfunction "1_5") (pintype "passive"))
    )
    (net (code "10") (name "Net-(NTC1AH-1)") (class "Default")
      (node (ref "C2") (pin "1") (pinfunction "1_1") (pintype "passive"))
      (node (ref "NTC1") (pin "4") (pinfunction "1_4") (pintype "passive"))
      (node (ref "R2") (pin "2") (pinfunction "2_2") (pintype "passive"))
      (node (ref "X1") (pin "24") (pinfunction "1_24") (pintype "passive"))
    )
    (net (code "11") (name "Net-(NTC1AI-1)") (class "Default")
      (node (ref "C20") (pin "1") (pinfunction "1_1") (pintype "passive"))
      (node (ref "NTC1") (pin "40") (pinfunction "1_40") (pintype "passive"))
      (node (ref "R20") (pin "2") (pinfunction "2_2") (pintype "passive"))
      (node (ref "X1") (pin "4") (pinfunction "1_4") (pintype "passive"))
    )
    (net (code "12") (name "Net-(NTC1AK-1)") (class "Default")
      (node (ref "C3") (pin "1") (pinfunction "1_1") (pintype "passive"))
      (node (ref "NTC1") (pin "6") (pinfunction "1_6") (pintype "passive"))
      (node (ref "R3") (pin "2") (pinfunction "2_2") (pintype "passive"))
      (node (ref "X1") (pin "23") (pinfunction "1_23") (pintype "passive"))
    )
    (net (code "13") (name "Net-(NTC1AM-1)") (class "Default")
      (node (ref "C4") (pin "1") (pinfunction "1_1") (pintype "passive"))
      (node (ref "NTC1") (pin "8") (pinfunction "1_8") (pintype "passive"))
      (node (ref "R4") (pin "2") (pinfunction "2_2") (pintype "passive"))
      (node (ref "X1") (pin "22") (pinfunction "1_22") (pintype "passive"))
    )
    (net (code "14") (name "Net-(NTC1B-1)") (class "Default")
      (node (ref "C5") (pin "1") (pinfunction "1_1") (pintype "passive"))
      (node (ref "NTC1") (pin "10") (pinfunction "1_10") (pintype "passive"))
      (node (ref "R5") (pin "2") (pinfunction "2_2") (pintype "passive"))
      (node (ref "X1") (pin "21") (pinfunction "1_21") (pintype "passive"))
    )
    (net (code "15") (name "Net-(NTC1D-1)") (class "Default")
      (node (ref "C6") (pin "1") (pinfunction "1_1") (pintype "passive"))
      (node (ref "NTC1") (pin "12") (pinfunction "1_12") (pintype "passive"))
      (node (ref "R6") (pin "2") (pinfunction "2_2") (pintype "passive"))
      (node (ref "X1") (pin "20") (pinfunction "1_20") (pintype "passive"))
    )
    (net (code "16") (name "Net-(NTC1F-1)") (class "Default")
      (node (ref "C7") (pin "1") (pinfunction "1_1") (pintype "passive"))
      (node (ref "NTC1") (pin "14") (pinfunction "1_14") (pintype "passive"))
      (node (ref "R7") (pin "2") (pinfunction "2_2") (pintype "passive"))
      (node (ref "X1") (pin "19") (pinfunction "1_19") (pintype "passive"))
    )
    (net (code "17") (name "Net-(NTC1H-1)") (class "Default")
      (node (ref "C8") (pin "1") (pinfunction "1_1") (pintype "passive"))
      (node (ref "NTC1") (pin "16") (pinfunction "1_16") (pintype "passive"))
      (node (ref "R8") (pin "2") (pinfunction "2_2") (pintype "passive"))
      (node (ref "X1") (pin "18") (pinfunction "1_18") (pintype "passive"))
    )
    (net (code "18") (name "Net-(NTC1J-1)") (class "Default")
      (node (ref "C9") (pin "1") (pinfunction "1_1") (pintype "passive"))
      (node (ref "NTC1") (pin "18") (pinfunction "1_18") (pintype "passive"))
      (node (ref "R9") (pin "2") (pinfunction "2_2") (pintype "passive"))
      (node (ref "X1") (pin "17") (pinfunction "1_17") (pintype "passive"))
    )
    (net (code "19") (name "Net-(NTC1L-1)") (class "Default")
      (node (ref "C1") (pin "1") (pinfunction "1_1") (pintype "passive"))
      (node (ref "NTC1") (pin "2") (pinfunction "1_2") (pintype "passive"))
      (node (ref "R1") (pin "2") (pinfunction "2_2") (pintype "passive"))
      (node (ref "X2") (pin "1") (pinfunction "1_1") (pintype "passive"))
    )
    (net (code "20") (name "Net-(NTC1M-1)") (class "Default")
      (node (ref "C10") (pin "1") (pinfunction "1_1") (pintype "passive"))
      (node (ref "NTC1") (pin "20") (pinfunction "1_20") (pintype "passive"))
      (node (ref "R10") (pin "2") (pinfunction "2_2") (pintype "passive"))
      (node (ref "X1") (pin "16") (pinfunction "1_16") (pintype "passive"))
    )
    (net (code "21") (name "Net-(NTC1O-1)") (class "Default")
      (node (ref "C11") (pin "1") (pinfunction "1_1") (pintype "passive"))
      (node (ref "NTC1") (pin "22") (pinfunction "1_22") (pintype "passive"))
      (node (ref "R11") (pin "2") (pinfunction "2_2") (pintype "passive"))
      (node (ref "X1") (pin "13") (pinfunction "1_13") (pintype "passive"))
    )
    (net (code "22") (name "Net-(NTC1Q-1)") (class "Default")
      (node (ref "C12") (pin "1") (pinfunction "1_1") (pintype "passive"))
      (node (ref "NTC1") (pin "24") (pinfunction "1_24") (pintype "passive"))
      (node (ref "R12") (pin "2") (pinfunction "2_2") (pintype "passive"))
      (node (ref "X1") (pin "12") (pinfunction "1_12") (pintype "passive"))
    )
    (net (code "23") (name "Net-(NTC1S-1)") (class "Default")
      (node (ref "C13") (pin "1") (pinfunction "1_1") (pintype "passive"))
      (node (ref "NTC1") (pin "26") (pinfunction "1_26") (pintype "passive"))
      (node (ref "R13") (pin "2") (pinfunction "2_2") (pintype "passive"))
      (node (ref "X1") (pin "11") (pinfunction "1_11") (pintype "passive"))
    )
    (net (code "24") (name "Net-(NTC1U-1)") (class "Default")
      (node (ref "C14") (pin "1") (pinfunction "1_1") (pintype "passive"))
      (node (ref "NTC1") (pin "28") (pinfunction "1_28") (pintype "passive"))
      (node (ref "R14") (pin "2") (pinfunction "2_2") (pintype "passive"))
      (node (ref "X1") (pin "10") (pinfunction "1_10") (pintype "passive"))
    )
    (net (code "25") (name "Net-(NTC1X-1)") (class "Default")
      (node (ref "C15") (pin "1") (pinfunction "1_1") (pintype "passive"))
      (node (ref "NTC1") (pin "30") (pinfunction "1_30") (pintype "passive"))
      (node (ref "R15") (pin "2") (pinfunction "2_2") (pintype "passive"))
      (node (ref "X1") (pin "9") (pinfunction "1_9") (pintype "passive"))
    )
    (net (code "26") (name "Net-(NTC1Z-1)") (class "Default")
      (node (ref "C16") (pin "1") (pinfunction "1_1") (pintype "passive"))
      (node (ref "NTC1") (pin "32") (pinfunction "1_32") (pintype "passive"))
      (node (ref "R16") (pin "2") (pinfunction "2_2") (pintype "passive"))
      (node (ref "X1") (pin "8") (pinfunction "1_8") (pintype "passive"))
    )
    (net (code "27") (name "Net-(NTC2AB-1)") (class "Default")
      (node (ref "C37") (pin "1") (pinfunction "1_1") (pintype "passive"))
      (node (ref "NTC2") (pin "34") (pinfunction "1_34") (pintype "passive"))
      (node (ref "R37") (pin "2") (pinfunction "2_2") (pintype "passive"))
      (node (ref "X3") (pin "7") (pinfunction "1_7") (pintype "passive"))
    )
    (net (code "28") (name "Net-(NTC2AD-1)") (class "Default")
      (node (ref "C38") (pin "1") (pinfunction "1_1") (pintype "passive"))
      (node (ref "NTC2") (pin "36") (pinfunction "1_36") (pintype "passive"))
      (node (ref "R38") (pin "2") (pinfunction "2_2") (pintype "passive"))
      (node (ref "X3") (pin "6") (pinfunction "1_6") (pintype "passive"))
    )
    (net (code "29") (name "Net-(NTC2AF-1)") (class "Default")
      (node (ref "C39") (pin "1") (pinfunction "1_1") (pintype "passive"))
      (node (ref "NTC2") (pin "38") (pinfunction "1_38") (pintype "passive"))
      (node (ref "R39") (pin "2") (pinfunction "2_2") (pintype "passive"))
      (node (ref "X3") (pin "5") (pinfunction "1_5") (pintype "passive"))
    )
    (net (code "30") (name "Net-(NTC2AH-1)") (class "Default")
      (node (ref "C22") (pin "1") (pinfunction "1_1") (pintype "passive"))
      (node (ref "NTC2") (pin "4") (pinfunction "1_4") (pintype "passive"))
      (node (ref "R22") (pin "2") (pinfunction "2_2") (pintype "passive"))
      (node (ref "X3") (pin "24") (pinfunction "1_24") (pintype "passive"))
    )
    (net (code "31") (name "Net-(NTC2AI-1)") (class "Default")
      (node (ref "C40") (pin "1") (pinfunction "1_1") (pintype "passive"))
      (node (ref "NTC2") (pin "40") (pinfunction "1_40") (pintype "passive"))
      (node (ref "R40") (pin "2") (pinfunction "2_2") (pintype "passive"))
      (node (ref "X3") (pin "4") (pinfunction "1_4") (pintype "passive"))
    )
    (net (code "32") (name "Net-(NTC2AK-1)") (class "Default")
      (node (ref "C23") (pin "1") (pinfunction "1_1") (pintype "passive"))
      (node (ref "NTC2") (pin "6") (pinfunction "1_6") (pintype "passive"))
      (node (ref "R23") (pin "2") (pinfunction "2_2") (pintype "passive"))
      (node (ref "X3") (pin "23") (pinfunction "1_23") (pintype "passive"))
    )
    (net (code "33") (name "Net-(NTC2AM-1)") (class "Default")
      (node (ref "C24") (pin "1") (pinfunction "1_1") (pintype "passive"))
      (node (ref "NTC2") (pin "8") (pinfunction "1_8") (pintype "passive"))
      (node (ref "R24") (pin "2") (pinfunction "2_2") (pintype "passive"))
      (node (ref "X3") (pin "22") (pinfunction "1_22") (pintype "passive"))
    )
    (net (code "34") (name "Net-(NTC2B-1)") (class "Default")
      (node (ref "C25") (pin "1") (pinfunction "1_1") (pintype "passive"))
      (node (ref "NTC2") (pin "10") (pinfunction "1_10") (pintype "passive"))
      (node (ref "R25") (pin "2") (pinfunction "2_2") (pintype "passive"))
      (node (ref "X3") (pin "21") (pinfunction "1_21") (pintype "passive"))
    )
    (net (code "35") (name "Net-(NTC2D-1)") (class "Default")
      (node (ref "C26") (pin "1") (pinfunction "1_1") (pintype "passive"))
      (node (ref "NTC2") (pin "12") (pinfunction "1_12") (pintype "passive"))
      (node (ref "R26") (pin "2") (pinfunction "2_2") (pintype "passive"))
      (node (ref "X3") (pin "20") (pinfunction "1_20") (pintype "passive"))
    )
    (net (code "36") (name "Net-(NTC2F-1)") (class "Default")
      (node (ref "C27") (pin "1") (pinfunction "1_1") (pintype "passive"))
      (node (ref "NTC2") (pin "14") (pinfunction "1_14") (pintype "passive"))
      (node (ref "R27") (pin "2") (pinfunction "2_2") (pintype "passive"))
      (node (ref "X3") (pin "19") (pinfunction "1_19") (pintype "passive"))
    )
    (net (code "37") (name "Net-(NTC2H-1)") (class "Default")
      (node (ref "C28") (pin "1") (pinfunction "1_1") (pintype "passive"))
      (node (ref "NTC2") (pin "16") (pinfunction "1_16") (pintype "passive"))
      (node (ref "R28") (pin "2") (pinfunction "2_2") (pintype "passive"))
      (node (ref "X3") (pin "18") (pinfunction "1_18") (pintype "passive"))
    )
    (net (code "38") (name "Net-(NTC2J-1)") (class "Default")
      (node (ref "C29") (pin "1") (pinfunction "1_1") (pintype "passive"))
      (node (ref "NTC2") (pin "18") (pinfunction "1_18") (pintype "passive"))
      (node (ref "R29") (pin "2") (pinfunction "2_2") (pintype "passive"))
      (node (ref "X3") (pin "17") (pinfunction "1_17") (pintype "passive"))
    )
    (net (code "39") (name "Net-(NTC2L-1)") (class "Default")
      (node (ref "C21") (pin "1") (pinfunction "1_1") (pintype "passive"))
      (node (ref "NTC2") (pin "2") (pinfunction "1_2") (pintype "passive"))
      (node (ref "R21") (pin "2") (pinfunction "2_2") (pintype "passive"))
      (node (ref "X4") (pin "1") (pinfunction "1_1") (pintype "passive"))
    )
    (net (code "40") (name "Net-(NTC2M-1)") (class "Default")
      (node (ref "C30") (pin "1") (pinfunction "1_1") (pintype "passive"))
      (node (ref "NTC2") (pin "20") (pinfunction "1_20") (pintype "passive"))
      (node (ref "R30") (pin "2") (pinfunction "2_2") (pintype "passive"))
      (node (ref "X3") (pin "16") (pinfunction "1_16") (pintype "passive"))
    )
    (net (code "41") (name "Net-(NTC2O-1)") (class "Default")
      (node (ref "C31") (pin "1") (pinfunction "1_1") (pintype "passive"))
      (node (ref "NTC2") (pin "22") (pinfunction "1_22") (pintype "passive"))
      (node (ref "R31") (pin "2") (pinfunction "2_2") (pintype "passive"))
      (node (ref "X3") (pin "13") (pinfunction "1_13") (pintype "passive"))
    )
    (net (code "42") (name "Net-(NTC2Q-1)") (class "Default")
      (node (ref "C32") (pin "1") (pinfunction "1_1") (pintype "passive"))
      (node (ref "NTC2") (pin "24") (pinfunction "1_24") (pintype "passive"))
      (node (ref "R32") (pin "2") (pinfunction "2_2") (pintype "passive"))
      (node (ref "X3") (pin "12") (pinfunction "1_12") (pintype "passive"))
    )
    (net (code "43") (name "Net-(NTC2S-1)") (class "Default")
      (node (ref "C33") (pin "1") (pinfunction "1_1") (pintype "passive"))
      (node (ref "NTC2") (pin "26") (pinfunction "1_26") (pintype "passive"))
      (node (ref "R33") (pin "2") (pinfunction "2_2") (pintype "passive"))
      (node (ref "X3") (pin "11") (pinfunction "1_11") (pintype "passive"))
    )
    (net (code "44") (name "Net-(NTC2U-1)") (class "Default")
      (node (ref "C34") (pin "1") (pinfunction "1_1") (pintype "passive"))
      (node (ref "NTC2") (pin "28") (pinfunction "1_28") (pintype "passive"))
      (node (ref "R34") (pin "2") (pinfunction "2_2") (pintype "passive"))
      (node (ref "X3") (pin "10") (pinfunction "1_10") (pintype "passive"))
    )
    (net (code "45") (name "Net-(NTC2X-1)") (class "Default")
      (node (ref "C35") (pin "1") (pinfunction "1_1") (pintype "passive"))
      (node (ref "NTC2") (pin "30") (pinfunction "1_30") (pintype "passive"))
      (node (ref "R35") (pin "2") (pinfunction "2_2") (pintype "passive"))
      (node (ref "X3") (pin "9") (pinfunction "1_9") (pintype "passive"))
    )
    (net (code "46") (name "Net-(NTC2Z-1)") (class "Default")
      (node (ref "C36") (pin "1") (pinfunction "1_1") (pintype "passive"))
      (node (ref "NTC2") (pin "32") (pinfunction "1_32") (pintype "passive"))
      (node (ref "R36") (pin "2") (pinfunction "2_2") (pintype "passive"))
      (node (ref "X3") (pin "8") (pinfunction "1_8") (pintype "passive"))
    )
    (net (code "47") (name "Net-(X2K-1)") (class "Default")
      (node (ref "X2") (pin "19") (pinfunction "1_19") (pintype "passive"))
      (node (ref "X7") (pin "4") (pinfunction "1_4") (pintype "passive"))
    )
    (net (code "48") (name "Net-(X2M-1)") (class "Default")
      (node (ref "X2") (pin "20") (pinfunction "1_20") (pintype "passive"))
      (node (ref "X7") (pin "3") (pinfunction "1_3") (pintype "passive"))
    )
    (net (code "49") (name "Net-(X4K-1)") (class "Default")
      (node (ref "X4") (pin "19") (pinfunction "1_19") (pintype "passive"))
      (node (ref "X8") (pin "4") (pinfunction "1_4") (pintype "passive"))
    )
    (net (code "50") (name "Net-(X4M-1)") (class "Default")
      (node (ref "X4") (pin "20") (pinfunction "1_20") (pintype "passive"))
      (node (ref "X8") (pin "3") (pinfunction "1_3") (pintype "passive"))
    )
    (net (code "51") (name "unconnected-(X1-Pad1)") (class "Default")
      (node (ref "X1") (pin "1") (pinfunction "1_1") (pintype "passive"))
    )
    (net (code "52") (name "unconnected-(X1F-1-Pad14)") (class "Default")
      (node (ref "X1") (pin "14") (pinfunction "1_14") (pintype "passive"))
    )
    (net (code "53") (name "unconnected-(X1G-1-Pad15)") (class "Default")
      (node (ref "X1") (pin "15") (pinfunction "1_15") (pintype "passive"))
    )
    (net (code "54") (name "unconnected-(X1R-1-Pad3)") (class "Default")
      (node (ref "X1") (pin "3") (pinfunction "1_3") (pintype "passive"))
    )
    (net (code "55") (name "unconnected-(X2C-1-Pad11)") (class "Default")
      (node (ref "X2") (pin "11") (pinfunction "1_11") (pintype "passive"))
    )
    (net (code "56") (name "unconnected-(X2D-1-Pad12)") (class "Default")
      (node (ref "X2") (pin "12") (pinfunction "1_12") (pintype "passive"))
    )
    (net (code "57") (name "unconnected-(X2E-1-Pad13)") (class "Default")
      (node (ref "X2") (pin "13") (pinfunction "1_13") (pintype "passive"))
    )
    (net (code "58") (name "unconnected-(X2F-1-Pad14)") (class "Default")
      (node (ref "X2") (pin "14") (pinfunction "1_14") (pintype "passive"))
    )
    (net (code "59") (name "unconnected-(X2G-1-Pad15)") (class "Default")
      (node (ref "X2") (pin "15") (pinfunction "1_15") (pintype "passive"))
    )
    (net (code "60") (name "unconnected-(X2H-1-Pad16)") (class "Default")
      (node (ref "X2") (pin "16") (pinfunction "1_16") (pintype "passive"))
    )
    (net (code "61") (name "unconnected-(X2I-1-Pad17)") (class "Default")
      (node (ref "X2") (pin "17") (pinfunction "1_17") (pintype "passive"))
    )
    (net (code "62") (name "unconnected-(X2J-1-Pad18)") (class "Default")
      (node (ref "X2") (pin "18") (pinfunction "1_18") (pintype "passive"))
    )
    (net (code "63") (name "unconnected-(X2L-1-Pad2)") (class "Default")
      (node (ref "X2") (pin "2") (pinfunction "1_2") (pintype "passive"))
    )
    (net (code "64") (name "unconnected-(X2N-1-Pad21)") (class "Default")
      (node (ref "X2") (pin "21") (pinfunction "1_21") (pintype "passive"))
    )
    (net (code "65") (name "unconnected-(X2O-1-Pad22)") (class "Default")
      (node (ref "X2") (pin "22") (pinfunction "1_22") (pintype "passive"))
    )
    (net (code "66") (name "unconnected-(X2P-1-Pad23)") (class "Default")
      (node (ref "X2") (pin "23") (pinfunction "1_23") (pintype "passive"))
    )
    (net (code "67") (name "unconnected-(X2R-1-Pad3)") (class "Default")
      (node (ref "X2") (pin "3") (pinfunction "1_3") (pintype "passive"))
    )
    (net (code "68") (name "unconnected-(X2S-1-Pad4)") (class "Default")
      (node (ref "X2") (pin "4") (pinfunction "1_4") (pintype "passive"))
    )
    (net (code "69") (name "unconnected-(X2T-1-Pad5)") (class "Default")
      (node (ref "X2") (pin "5") (pinfunction "1_5") (pintype "passive"))
    )
    (net (code "70") (name "unconnected-(X2U-1-Pad6)") (class "Default")
      (node (ref "X2") (pin "6") (pinfunction "1_6") (pintype "passive"))
    )
    (net (code "71") (name "unconnected-(X2V-1-Pad7)") (class "Default")
      (node (ref "X2") (pin "7") (pinfunction "1_7") (pintype "passive"))
    )
    (net (code "72") (name "unconnected-(X2W-1-Pad8)") (class "Default")
      (node (ref "X2") (pin "8") (pinfunction "1_8") (pintype "passive"))
    )
    (net (code "73") (name "unconnected-(X2X-1-Pad9)") (class "Default")
      (node (ref "X2") (pin "9") (pinfunction "1_9") (pintype "passive"))
    )
    (net (code "74") (name "unconnected-(X3-Pad1)") (class "Default")
      (node (ref "X3") (pin "1") (pinfunction "1_1") (pintype "passive"))
    )
    (net (code "75") (name "unconnected-(X3F-1-Pad14)") (class "Default")
      (node (ref "X3") (pin "14") (pinfunction "1_14") (pintype "passive"))
    )
    (net (code "76") (name "unconnected-(X3G-1-Pad15)") (class "Default")
      (node (ref "X3") (pin "15") (pinfunction "1_15") (pintype "passive"))
    )
    (net (code "77") (name "unconnected-(X3R-1-Pad3)") (class "Default")
      (node (ref "X3") (pin "3") (pinfunction "1_3") (pintype "passive"))
    )
    (net (code "78") (name "unconnected-(X4C-1-Pad11)") (class "Default")
      (node (ref "X4") (pin "11") (pinfunction "1_11") (pintype "passive"))
    )
    (net (code "79") (name "unconnected-(X4D-1-Pad12)") (class "Default")
      (node (ref "X4") (pin "12") (pinfunction "1_12") (pintype "passive"))
    )
    (net (code "80") (name "unconnected-(X4E-1-Pad13)") (class "Default")
      (node (ref "X4") (pin "13") (pinfunction "1_13") (pintype "passive"))
    )
    (net (code "81") (name "unconnected-(X4F-1-Pad14)") (class "Default")
      (node (ref "X4") (pin "14") (pinfunction "1_14") (pintype "passive"))
    )
    (net (code "82") (name "unconnected-(X4G-1-Pad15)") (class "Default")
      (node (ref "X4") (pin "15") (pinfunction "1_15") (pintype "passive"))
    )
    (net (code "83") (name "unconnected-(X4H-1-Pad16)") (class "Default")
      (node (ref "X4") (pin "16") (pinfunction "1_16") (pintype "passive"))
    )
    (net (code "84") (name "unconnected-(X4I-1-Pad17)") (class "Default")
      (node (ref "X4") (pin "17") (pinfunction "1_17") (pintype "passive"))
    )
    (net (code "85") (name "unconnected-(X4J-1-Pad18)") (class "Default")
      (node (ref "X4") (pin "18") (pinfunction "1_18") (pintype "passive"))
    )
    (net (code "86") (name "unconnected-(X4L-1-Pad2)") (class "Default")
      (node (ref "X4") (pin "2") (pinfunction "1_2") (pintype "passive"))
    )
    (net (code "87") (name "unconnected-(X4N-1-Pad21)") (class "Default")
      (node (ref "X4") (pin "21") (pinfunction "1_21") (pintype "passive"))
    )
    (net (code "88") (name "unconnected-(X4O-1-Pad22)") (class "Default")
      (node (ref "X4") (pin "22") (pinfunction "1_22") (pintype "passive"))
    )
    (net (code "89") (name "unconnected-(X4P-1-Pad23)") (class "Default")
      (node (ref "X4") (pin "23") (pinfunction "1_23") (pintype "passive"))
    )
    (net (code "90") (name "unconnected-(X4R-1-Pad3)") (class "Default")
      (node (ref "X4") (pin "3") (pinfunction "1_3") (pintype "passive"))
    )
    (net (code "91") (name "unconnected-(X4S-1-Pad4)") (class "Default")
      (node (ref "X4") (pin "4") (pinfunction "1_4") (pintype "passive"))
    )
    (net (code "92") (name "unconnected-(X4T-1-Pad5)") (class "Default")
      (node (ref "X4") (pin "5") (pinfunction "1_5") (pintype "passive"))
    )
    (net (code "93") (name "unconnected-(X4U-1-Pad6)") (class "Default")
      (node (ref "X4") (pin "6") (pinfunction "1_6") (pintype "passive"))
    )
    (net (code "94") (name "unconnected-(X4V-1-Pad7)") (class "Default")
      (node (ref "X4") (pin "7") (pinfunction "1_7") (pintype "passive"))
    )
    (net (code "95") (name "unconnected-(X4W-1-Pad8)") (class "Default")
      (node (ref "X4") (pin "8") (pinfunction "1_8") (pintype "passive"))
    )
    (net (code "96") (name "unconnected-(X4X-1-Pad9)") (class "Default")
      (node (ref "X4") (pin "9") (pinfunction "1_9") (pintype "passive"))
    )
  )
)
